# DSO_IO.net
KiCad netlist of a schematic drawn in Altium Designer
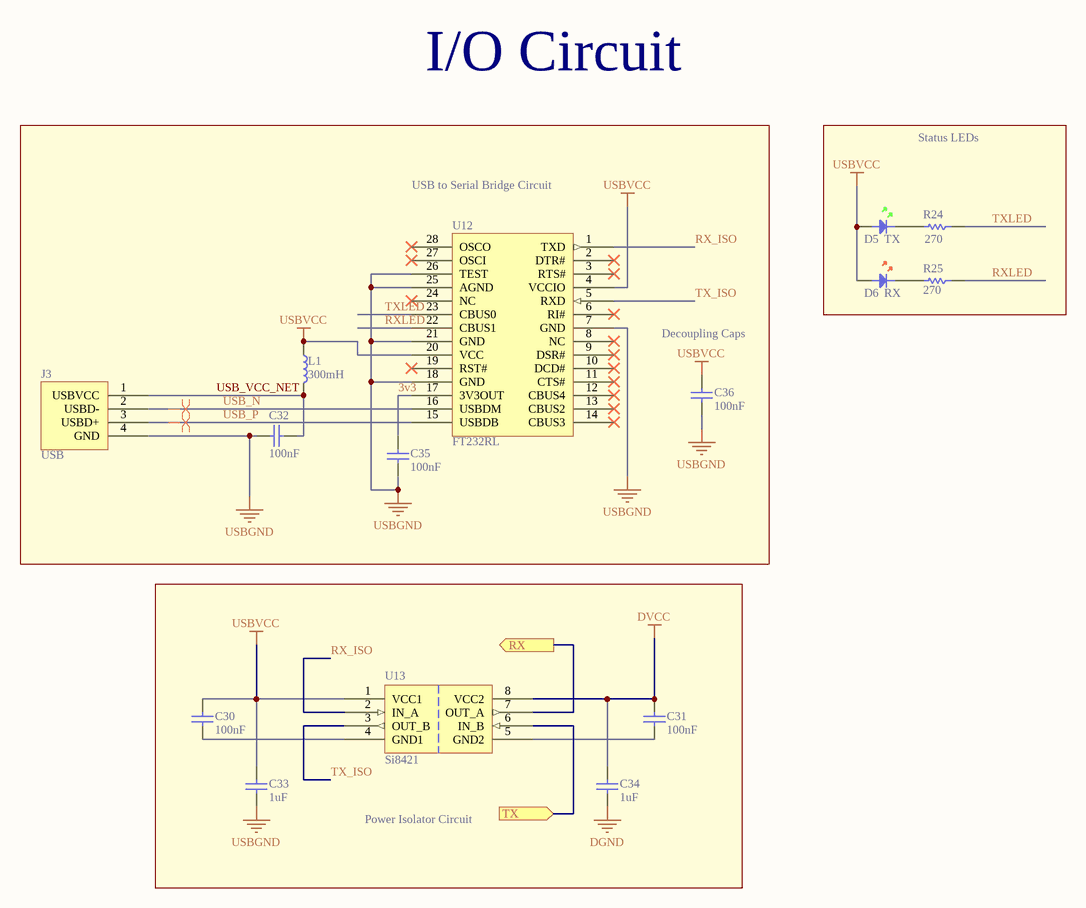
[diagram p0: DSO_IO.SchDoc]

(export (version "E")
  (design (tool "Eeschema 10.0.6"))
  (components
    (comp (ref "C30")
      (value "100nF")
      (footprint "0805C")
      (description "Capacitor")
      (fields (field (name "REVIEWED BY") "RM - 2018/08/05"))
      (libsource (lib "DSO") (part "C"))
    )
    (comp (ref "C31")
      (value "100nF")
      (footprint "0805C")
      (description "Capacitor")
      (fields (field (name "REVIEWED BY") "RM - 2018/08/05"))
      (libsource (lib "DSO") (part "C"))
    )
    (comp (ref "C32")
      (value "100nF")
      (footprint "0805C")
      (description "Capacitor")
      (fields (field (name "REVIEWED BY") "RM - 2018/08/05"))
      (libsource (lib "DSO") (part "C"))
    )
    (comp (ref "C33")
      (value "1uF")
      (footprint "0805C")
      (description "Capacitor")
      (fields (field (name "REVIEWED BY") "RM - 2018/08/05"))
      (libsource (lib "DSO") (part "C"))
    )
    (comp (ref "C34")
      (value "1uF")
      (footprint "0805C")
      (description "Capacitor")
      (fields (field (name "REVIEWED BY") "RM - 2018/08/05"))
      (libsource (lib "DSO") (part "C"))
    )
    (comp (ref "C35")
      (value "100nF")
      (footprint "0805C")
      (description "Capacitor")
      (fields (field (name "REVIEWED BY") "RM - 2018/08/05"))
      (libsource (lib "DSO") (part "C"))
    )
    (comp (ref "C36")
      (value "100nF")
      (footprint "0805C")
      (description "Capacitor")
      (fields (field (name "REVIEWED BY") "RM - 2018/08/05"))
      (libsource (lib "DSO") (part "C"))
    )
    (comp (ref "D5")
      (value "TX")
      (footprint "0805D-GREEN")
      (description "Light Emitting Diode")
      (fields (field (name "REVIEWED BY") "RM - 2018/08/05"))
      (libsource (lib "DSO") (part "LED GREEN"))
    )
    (comp (ref "D6")
      (value "RX")
      (footprint "0805D-RED")
      (description "Light Emitting Diode")
      (fields (field (name "REVIEWED BY") "RM - 2018/08/05"))
      (libsource (lib "DSO") (part "LED RED"))
    )
    (comp (ref "J3")
      (value "USB")
      (footprint "USBPLUG")
      (description "USB B Type Connector")
      (fields (field (name "REVIEWED BY") "RM - 2018/08/05"))
      (libsource (lib "DSO") (part "USBPLUG"))
    )
    (comp (ref "L1")
      (value "300mH")
      (footprint "0805")
      (description "Inductor")
      (fields (field (name "REVIEWED BY") "RM - 2018/08/05"))
      (libsource (lib "DSO") (part "I"))
    )
    (comp (ref "R24")
      (value "270")
      (footprint "0805")
      (description "Resistor")
      (fields (field (name "REVIEWED BY") "RM - 2018/08/05"))
      (libsource (lib "DSO") (part "R"))
    )
    (comp (ref "R25")
      (value "270")
      (footprint "0805")
      (description "Resistor")
      (fields (field (name "REVIEWED BY") "RM - 2018/08/05"))
      (libsource (lib "DSO") (part "R"))
    )
    (comp (ref "U12")
      (value "FT232RL")
      (footprint "SSOP-28")
      (description "USB to Serial bridge")
      (fields (field (name "REVIEWED BY") "RM - 2018/08/05"))
      (libsource (lib "DSO") (part "FT232RL"))
    )
    (comp (ref "U13")
      (value "Si8421")
      (footprint "SOIC-8")
      (description "Dual Channel Digital Isolator Both Ways")
      (fields (field (name "REVIEWED BY") "RM - 2018/08/05"))
      (libsource (lib "DSO") (part "Si8421"))
    )
  )
  (nets
    (net (code "1") (name "/3v3") (class "Default")
      (node (ref "C35") (pin "1") (pinfunction "1_1") (pintype "passive"))
      (node (ref "U12") (pin "17") (pinfunction "3V3OUT_17") (pintype "passive"))
    )
    (net (code "2") (name "/RX") (class "Default")
      (node (ref "U13") (pin "7") (pinfunction "OUT_A_7") (pintype "output"))
    )
    (net (code "3") (name "/RXLED") (class "Default")
      (node (ref "R25") (pin "1") (pintype "passive"))
      (node (ref "U12") (pin "22") (pinfunction "CBUS1_22") (pintype "passive"))
    )
    (net (code "4") (name "/RX_ISO") (class "Default")
      (node (ref "U12") (pin "1") (pinfunction "TXD_1") (pintype "output"))
      (node (ref "U13") (pin "2") (pinfunction "IN_A_2") (pintype "input"))
    )
    (net (code "5") (name "/TX") (class "Default")
      (node (ref "U13") (pin "6") (pinfunction "IN_B_6") (pintype "input"))
    )
    (net (code "6") (name "/TXLED") (class "Default")
      (node (ref "R24") (pin "1") (pintype "passive"))
      (node (ref "U12") (pin "23") (pinfunction "CBUS0_23") (pintype "passive"))
    )
    (net (code "7") (name "/TX_ISO") (class "Default")
      (node (ref "U12") (pin "5") (pinfunction "RXD_5") (pintype "input"))
      (node (ref "U13") (pin "3") (pinfunction "OUT_B_3") (pintype "output"))
    )
    (net (code "8") (name "/USB_N") (class "Default")
      (node (ref "J3") (pin "2") (pinfunction "USBD-_2") (pintype "passive"))
      (node (ref "U12") (pin "16") (pinfunction "USBDM_16") (pintype "passive"))
    )
    (net (code "9") (name "/USB_P") (class "Default")
      (node (ref "J3") (pin "3") (pinfunction "USBD+_3") (pintype "passive"))
      (node (ref "U12") (pin "15") (pinfunction "USBDB_15") (pintype "passive"))
    )
    (net (code "10") (name "/USB_VCC_NET") (class "Default")
      (node (ref "C32") (pin "1") (pinfunction "1_1") (pintype "passive"))
      (node (ref "J3") (pin "1") (pinfunction "USBVCC_1") (pintype "passive"))
      (node (ref "L1") (pin "2") (pinfunction "2_2") (pintype "passive"))
    )
    (net (code "11") (name "DGND") (class "Default")
      (node (ref "C34") (pin "1") (pinfunction "1_1") (pintype "passive"))
    )
    (net (code "12") (name "DVCC") (class "Default")
      (node (ref "C31") (pin "1") (pinfunction "1_1") (pintype "passive"))
      (node (ref "C34") (pin "2") (pinfunction "2_2") (pintype "passive"))
      (node (ref "U13") (pin "8") (pinfunction "VCC2_8") (pintype "passive"))
    )
    (net (code "13") (name "Net-(D5-PadK)") (class "Default")
      (node (ref "D5") (pin "K") (pinfunction "K_K") (pintype "passive"))
      (node (ref "R24") (pin "2") (pintype "passive"))
    )
    (net (code "14") (name "Net-(D6-PadK)") (class "Default")
      (node (ref "D6") (pin "K") (pinfunction "K_K") (pintype "passive"))
      (node (ref "R25") (pin "2") (pintype "passive"))
    )
    (net (code "15") (name "Net-(U13-GND1)") (class "Default")
      (node (ref "C30") (pin "2") (pinfunction "2_2") (pintype "passive"))
      (node (ref "U13") (pin "4") (pinfunction "GND1_4") (pintype "passive"))
    )
    (net (code "16") (name "Net-(U13-GND2)") (class "Default")
      (node (ref "C31") (pin "2") (pinfunction "2_2") (pintype "passive"))
      (node (ref "U13") (pin "5") (pinfunction "GND2_5") (pintype "passive"))
    )
    (net (code "17") (name "USBGND") (class "Default")
      (node (ref "C32") (pin "2") (pinfunction "2_2") (pintype "passive"))
      (node (ref "C33") (pin "2") (pinfunction "2_2") (pintype "passive"))
      (node (ref "C35") (pin "2") (pinfunction "2_2") (pintype "passive"))
      (node (ref "C36") (pin "2") (pinfunction "2_2") (pintype "passive"))
      (node (ref "J3") (pin "4") (pinfunction "GND_4") (pintype "passive"))
      (node (ref "U12") (pin "18") (pinfunction "GND_18") (pintype "passive"))
      (node (ref "U12") (pin "21") (pinfunction "GND_21") (pintype "passive"))
      (node (ref "U12") (pin "25") (pinfunction "AGND_25") (pintype "passive"))
      (node (ref "U12") (pin "26") (pinfunction "TEST_26") (pintype "passive"))
      (node (ref "U12") (pin "7") (pinfunction "GND_7") (pintype "passive"))
    )
    (net (code "18") (name "USBVCC") (class "Default")
      (node (ref "C30") (pin "1") (pinfunction "1_1") (pintype "passive"))
      (node (ref "C33") (pin "1") (pinfunction "1_1") (pintype "passive"))
      (node (ref "C36") (pin "1") (pinfunction "1_1") (pintype "passive"))
      (node (ref "D5") (pin "A") (pinfunction "A_A") (pintype "passive"))
      (node (ref "D6") (pin "A") (pinfunction "A_A") (pintype "passive"))
      (node (ref "L1") (pin "1") (pinfunction "1_1") (pintype "passive"))
      (node (ref "U12") (pin "20") (pinfunction "VCC_20") (pintype "passive"))
      (node (ref "U12") (pin "4") (pinfunction "VCCIO_4") (pintype "passive"))
      (node (ref "U13") (pin "1") (pinfunction "VCC1_1") (pintype "passive"))
    )
    (net (code "19") (name "unconnected-(U12-CBUS2-Pad13)") (class "Default")
      (node (ref "U12") (pin "13") (pinfunction "CBUS2_13") (pintype "passive+no_connect"))
    )
    (net (code "20") (name "unconnected-(U12-CBUS3-Pad14)") (class "Default")
      (node (ref "U12") (pin "14") (pinfunction "CBUS3_14") (pintype "passive+no_connect"))
    )
    (net (code "21") (name "unconnected-(U12-CBUS4-Pad12)") (class "Default")
      (node (ref "U12") (pin "12") (pinfunction "CBUS4_12") (pintype "passive+no_connect"))
    )
    (net (code "22") (name "unconnected-(U12-CTS#-Pad11)") (class "Default")
      (node (ref "U12") (pin "11") (pinfunction "CTS#_11") (pintype "passive+no_connect"))
    )
    (net (code "23") (name "unconnected-(U12-DCD#-Pad10)") (class "Default")
      (node (ref "U12") (pin "10") (pinfunction "DCD#_10") (pintype "passive+no_connect"))
    )
    (net (code "24") (name "unconnected-(U12-DSR#-Pad9)") (class "Default")
      (node (ref "U12") (pin "9") (pinfunction "DSR#_9") (pintype "passive+no_connect"))
    )
    (net (code "25") (name "unconnected-(U12-DTR#-Pad2)") (class "Default")
      (node (ref "U12") (pin "2") (pinfunction "DTR#_2") (pintype "passive+no_connect"))
    )
    (net (code "26") (name "unconnected-(U12-NC-Pad8)") (class "Default")
      (node (ref "U12") (pin "8") (pinfunction "NC_8") (pintype "passive+no_connect"))
    )
    (net (code "27") (name "unconnected-(U12-NC-Pad24)") (class "Default")
      (node (ref "U12") (pin "24") (pinfunction "NC_24") (pintype "passive+no_connect"))
    )
    (net (code "28") (name "unconnected-(U12-OSCI-Pad27)") (class "Default")
      (node (ref "U12") (pin "27") (pinfunction "OSCI_27") (pintype "passive+no_connect"))
    )
    (net (code "29") (name "unconnected-(U12-OSCO-Pad28)") (class "Default")
      (node (ref "U12") (pin "28") (pinfunction "OSCO_28") (pintype "passive+no_connect"))
    )
    (net (code "30") (name "unconnected-(U12-RI#-Pad6)") (class "Default")
      (node (ref "U12") (pin "6") (pinfunction "RI#_6") (pintype "passive+no_connect"))
    )
    (net (code "31") (name "unconnected-(U12-RST#-Pad19)") (class "Default")
      (node (ref "U12") (pin "19") (pinfunction "RST#_19") (pintype "passive+no_connect"))
    )
    (net (code "32") (name "unconnected-(U12-RTS#-Pad3)") (class "Default")
      (node (ref "U12") (pin "3") (pinfunction "RTS#_3") (pintype "passive+no_connect"))
    )
  )
)
